# GPIOExpander.net
KiCad netlist of a schematic drawn in Altium Designer
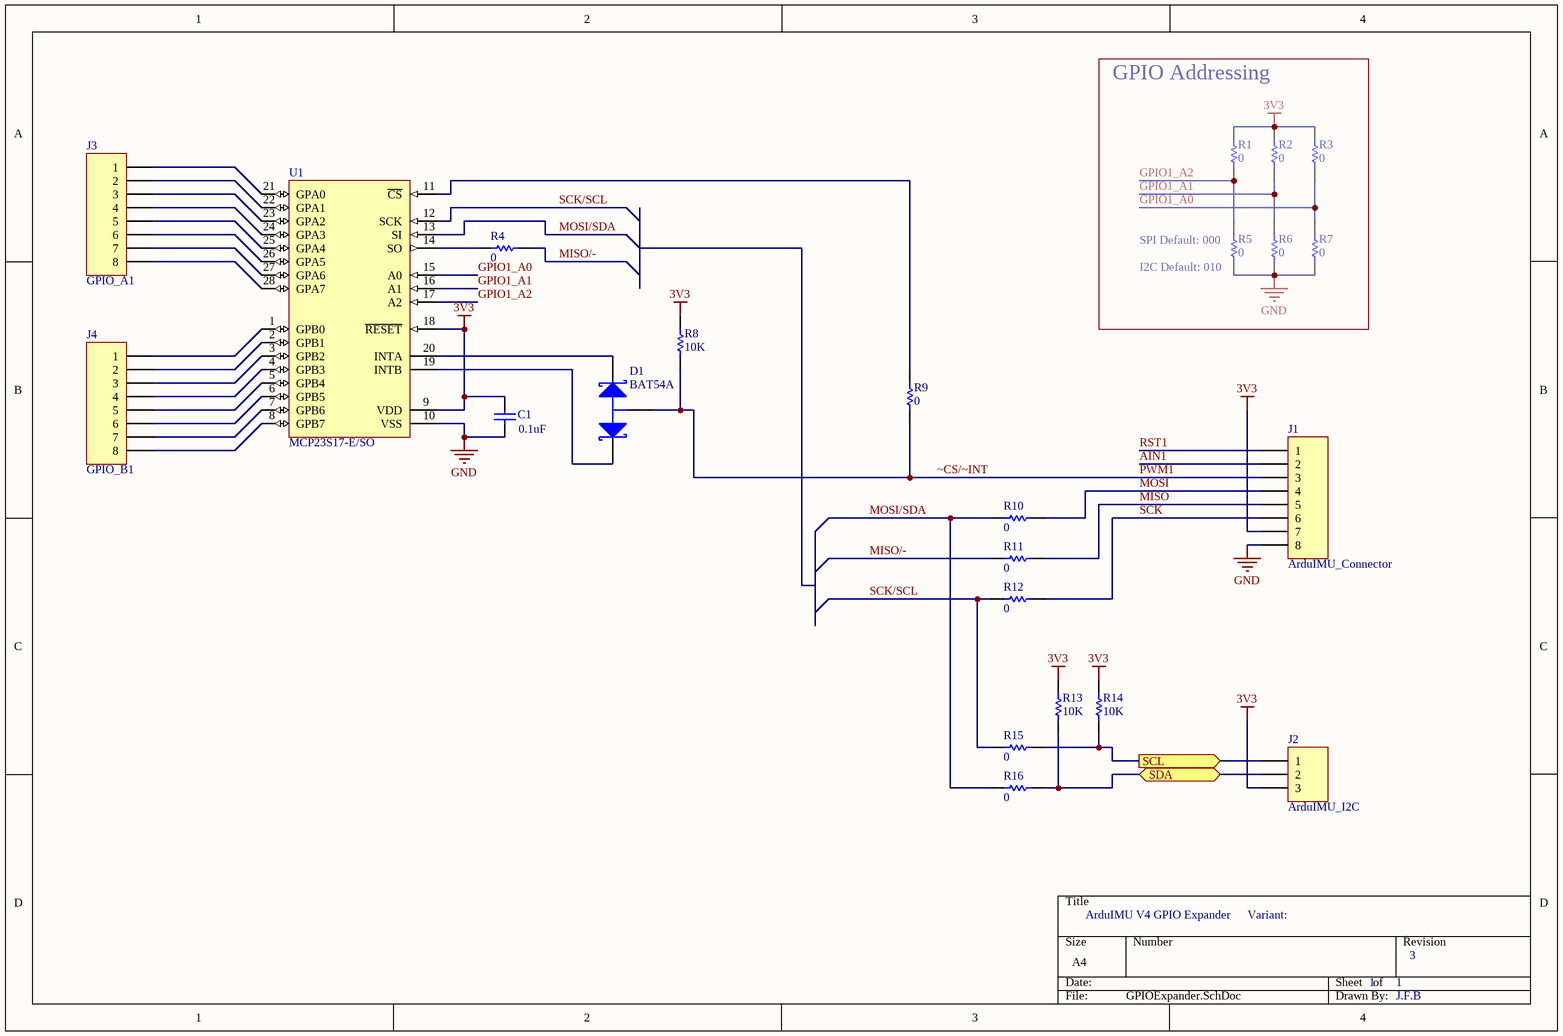
[diagram p0: GPIOExpander.SchDoc]

(export (version "E")
  (design (tool "Eeschema 10.0.6"))
  (components
    (comp (ref "C1")
      (value "0.1uF")
      (footprint "6-0805")
      (description "Capacitor")
      (fields (field (name "Comment") "Cap") (field (name "PUBLISHER") "Altium Limited"))
      (libsource (lib "Miscellaneous Devices") (part "Cap"))
    )
    (comp (ref "D1")
      (value "BAT54A")
      (footprint "SOT23_N")
      (description "Schottky Barrier Double Diode")
      (fields (field (name "PUBLISHER") "Altium Limited"))
      (libsource (lib "Philips Discrete Diode - Schottky") (part "BAT54A"))
    )
    (comp (ref "J1")
      (value "ArduIMU_Connector")
      (footprint "HDR1X8")
      (description "Header, 8-Pin")
      (fields (field (name "PUBLISHER") "Altium Limited"))
      (libsource (lib "Miscellaneous Connectors") (part "Header 8"))
    )
    (comp (ref "J2")
      (value "ArduIMU_I2C")
      (footprint "HDR1X3")
      (description "Header, 3-Pin")
      (fields (field (name "PUBLISHER") "Altium Limited"))
      (libsource (lib "Miscellaneous Connectors") (part "Header 3"))
    )
    (comp (ref "J3")
      (value "GPIO_A1")
      (footprint "HDR1X8")
      (description "Header, 8-Pin")
      (fields (field (name "PUBLISHER") "Altium Limited"))
      (libsource (lib "") (part "Header 8_1"))
    )
    (comp (ref "J4")
      (value "GPIO_B1")
      (footprint "HDR1X8")
      (description "Header, 8-Pin")
      (fields (field (name "PUBLISHER") "Altium Limited"))
      (libsource (lib "") (part "Header 8_1"))
    )
    (comp (ref "R1")
      (value "0")
      (footprint "6-0805")
      (description "Thick Film Chip Resistor, 1 Ohm to 10M Ohm Range, 5% Tolerance, 0805 Size, 0.125 W")
      (fields (field (name "PUBLISHER") "Altium Limited"))
      (libsource (lib "Panasonic Resistor") (part "ERJ6GE"))
    )
    (comp (ref "R2")
      (value "0")
      (footprint "6-0805")
      (description "Thick Film Chip Resistor, 1 Ohm to 10M Ohm Range, 5% Tolerance, 0805 Size, 0.125 W")
      (fields (field (name "PUBLISHER") "Altium Limited"))
      (libsource (lib "Panasonic Resistor") (part "ERJ6GE"))
    )
    (comp (ref "R3")
      (value "0")
      (footprint "6-0805")
      (description "Thick Film Chip Resistor, 1 Ohm to 10M Ohm Range, 5% Tolerance, 0805 Size, 0.125 W")
      (fields (field (name "PUBLISHER") "Altium Limited"))
      (libsource (lib "Panasonic Resistor") (part "ERJ6GE"))
    )
    (comp (ref "R4")
      (value "0")
      (footprint "6-0805")
      (description "Thick Film Chip Resistor, 1 Ohm to 10M Ohm Range, 5% Tolerance, 0805 Size, 0.125 W")
      (fields (field (name "PUBLISHER") "Altium Limited"))
      (libsource (lib "Panasonic Resistor") (part "ERJ6GE"))
    )
    (comp (ref "R5")
      (value "0")
      (footprint "6-0805")
      (description "Thick Film Chip Resistor, 1 Ohm to 10M Ohm Range, 5% Tolerance, 0805 Size, 0.125 W")
      (fields (field (name "PUBLISHER") "Altium Limited"))
      (libsource (lib "Panasonic Resistor") (part "ERJ6GE"))
    )
    (comp (ref "R6")
      (value "0")
      (footprint "6-0805")
      (description "Thick Film Chip Resistor, 1 Ohm to 10M Ohm Range, 5% Tolerance, 0805 Size, 0.125 W")
      (fields (field (name "PUBLISHER") "Altium Limited"))
      (libsource (lib "Panasonic Resistor") (part "ERJ6GE"))
    )
    (comp (ref "R7")
      (value "0")
      (footprint "6-0805")
      (description "Thick Film Chip Resistor, 1 Ohm to 10M Ohm Range, 5% Tolerance, 0805 Size, 0.125 W")
      (fields (field (name "PUBLISHER") "Altium Limited"))
      (libsource (lib "Panasonic Resistor") (part "ERJ6GE"))
    )
    (comp (ref "R8")
      (value "10K")
      (footprint "8-1206")
      (description "Thick Film Chip Resistor, 1 Ohm to 10M Ohm Range, 5% Tolerance, 1206 Size, 0.25 W")
      (fields (field (name "PUBLISHER") "Altium Limited"))
      (libsource (lib "Panasonic Resistor") (part "ERJ8GE"))
    )
    (comp (ref "R9")
      (value "0")
      (footprint "6-0805")
      (description "Thick Film Chip Resistor, 1 Ohm to 10M Ohm Range, 5% Tolerance, 0805 Size, 0.125 W")
      (fields (field (name "PUBLISHER") "Altium Limited"))
      (libsource (lib "Panasonic Resistor") (part "ERJ6GE"))
    )
    (comp (ref "R10")
      (value "0")
      (footprint "6-0805")
      (description "Thick Film Chip Resistor, 1 Ohm to 10M Ohm Range, 5% Tolerance, 0805 Size, 0.125 W")
      (fields (field (name "PUBLISHER") "Altium Limited"))
      (libsource (lib "Panasonic Resistor") (part "ERJ6GE"))
    )
    (comp (ref "R11")
      (value "0")
      (footprint "6-0805")
      (description "Thick Film Chip Resistor, 1 Ohm to 10M Ohm Range, 5% Tolerance, 0805 Size, 0.125 W")
      (fields (field (name "PUBLISHER") "Altium Limited"))
      (libsource (lib "Panasonic Resistor") (part "ERJ6GE"))
    )
    (comp (ref "R12")
      (value "0")
      (footprint "6-0805")
      (description "Thick Film Chip Resistor, 1 Ohm to 10M Ohm Range, 5% Tolerance, 0805 Size, 0.125 W")
      (fields (field (name "PUBLISHER") "Altium Limited"))
      (libsource (lib "Panasonic Resistor") (part "ERJ6GE"))
    )
    (comp (ref "R13")
      (value "10K")
      (footprint "8-1206")
      (description "Thick Film Chip Resistor, 1 Ohm to 10M Ohm Range, 5% Tolerance, 1206 Size, 0.25 W")
      (fields (field (name "PUBLISHER") "Altium Limited"))
      (libsource (lib "Panasonic Resistor") (part "ERJ8GE"))
    )
    (comp (ref "R14")
      (value "10K")
      (footprint "8-1206")
      (description "Thick Film Chip Resistor, 1 Ohm to 10M Ohm Range, 5% Tolerance, 1206 Size, 0.25 W")
      (fields (field (name "PUBLISHER") "Altium Limited"))
      (libsource (lib "Panasonic Resistor") (part "ERJ8GE"))
    )
    (comp (ref "R15")
      (value "0")
      (footprint "6-0805")
      (description "Thick Film Chip Resistor, 1 Ohm to 10M Ohm Range, 5% Tolerance, 0805 Size, 0.125 W")
      (fields (field (name "PUBLISHER") "Altium Limited"))
      (libsource (lib "Panasonic Resistor") (part "ERJ6GE"))
    )
    (comp (ref "R16")
      (value "0")
      (footprint "6-0805")
      (description "Thick Film Chip Resistor, 1 Ohm to 10M Ohm Range, 5% Tolerance, 0805 Size, 0.125 W")
      (fields (field (name "PUBLISHER") "Altium Limited"))
      (libsource (lib "Panasonic Resistor") (part "ERJ6GE"))
    )
    (comp (ref "U1")
      (value "MCP23S17-E/SO")
      (footprint "SOIC-SO28_N")
      (description "16-Bit I/O Expander with Serial Interface, 28-Pin SOIC, Extended Temperature")
      (fields (field (name "PUBLISHER") "Altium Limited"))
      (libsource (lib "Microchip Interface") (part "MCP23S17-E/SO"))
    )
  )
  (nets
    (net (code "1") (name "/AIN1") (class "Default")
      (node (ref "J1") (pin "2") (pinfunction "2_2") (pintype "passive"))
    )
    (net (code "2") (name "/GPIO1_A0") (class "Default")
      (node (ref "R3") (pin "1") (pinfunction "1_1") (pintype "passive"))
      (node (ref "R7") (pin "2") (pinfunction "2_2") (pintype "passive"))
      (node (ref "U1") (pin "15") (pinfunction "A0_15") (pintype "input"))
    )
    (net (code "3") (name "/GPIO1_A1") (class "Default")
      (node (ref "R2") (pin "1") (pinfunction "1_1") (pintype "passive"))
      (node (ref "R6") (pin "2") (pinfunction "2_2") (pintype "passive"))
      (node (ref "U1") (pin "16") (pinfunction "A1_16") (pintype "input"))
    )
    (net (code "4") (name "/GPIO1_A2") (class "Default")
      (node (ref "R1") (pin "1") (pinfunction "1_1") (pintype "passive"))
      (node (ref "R5") (pin "2") (pinfunction "2_2") (pintype "passive"))
      (node (ref "U1") (pin "17") (pinfunction "A2_17") (pintype "input"))
    )
    (net (code "5") (name "/MISO") (class "Default")
      (node (ref "J1") (pin "5") (pinfunction "5_5") (pintype "passive"))
      (node (ref "R11") (pin "2") (pinfunction "2_2") (pintype "passive"))
    )
    (net (code "6") (name "/MISO{slash}-") (class "Default")
      (node (ref "R11") (pin "1") (pinfunction "1_1") (pintype "passive"))
      (node (ref "R4") (pin "2") (pinfunction "2_2") (pintype "passive"))
    )
    (net (code "7") (name "/MOSI") (class "Default")
      (node (ref "J1") (pin "4") (pinfunction "4_4") (pintype "passive"))
      (node (ref "R10") (pin "2") (pinfunction "2_2") (pintype "passive"))
    )
    (net (code "8") (name "/MOSI{slash}SDA") (class "Default")
      (node (ref "R10") (pin "1") (pinfunction "1_1") (pintype "passive"))
      (node (ref "R16") (pin "1") (pinfunction "1_1") (pintype "passive"))
      (node (ref "U1") (pin "13") (pinfunction "SI_13") (pintype "input"))
    )
    (net (code "9") (name "/PWM1") (class "Default")
      (node (ref "D1") (pin "3") (pinfunction "A_3") (pintype "passive"))
      (node (ref "J1") (pin "3") (pinfunction "3_3") (pintype "passive"))
      (node (ref "R8") (pin "2") (pinfunction "2_2") (pintype "passive"))
      (node (ref "R9") (pin "1") (pinfunction "1_1") (pintype "passive"))
    )
    (net (code "10") (name "/RST1") (class "Default")
      (node (ref "J1") (pin "1") (pinfunction "1_1") (pintype "passive"))
    )
    (net (code "11") (name "/SCK") (class "Default")
      (node (ref "J1") (pin "6") (pinfunction "6_6") (pintype "passive"))
      (node (ref "R12") (pin "2") (pinfunction "2_2") (pintype "passive"))
    )
    (net (code "12") (name "/SCK{slash}SCL") (class "Default")
      (node (ref "R12") (pin "1") (pinfunction "1_1") (pintype "passive"))
      (node (ref "R15") (pin "1") (pinfunction "1_1") (pintype "passive"))
      (node (ref "U1") (pin "12") (pinfunction "SCK_12") (pintype "input"))
    )
    (net (code "13") (name "/SCL") (class "Default")
      (node (ref "J2") (pin "1") (pinfunction "1_1") (pintype "passive"))
      (node (ref "R14") (pin "2") (pinfunction "2_2") (pintype "passive"))
      (node (ref "R15") (pin "2") (pinfunction "2_2") (pintype "passive"))
    )
    (net (code "14") (name "/SDA") (class "Default")
      (node (ref "J2") (pin "2") (pinfunction "2_2") (pintype "passive"))
      (node (ref "R13") (pin "2") (pinfunction "2_2") (pintype "passive"))
      (node (ref "R16") (pin "2") (pinfunction "2_2") (pintype "passive"))
    )
    (net (code "15") (name "3V3") (class "Default")
      (node (ref "C1") (pin "2") (pinfunction "2_2") (pintype "passive"))
      (node (ref "J1") (pin "7") (pinfunction "7_7") (pintype "passive"))
      (node (ref "J2") (pin "3") (pinfunction "3_3") (pintype "passive"))
      (node (ref "R1") (pin "2") (pinfunction "2_2") (pintype "passive"))
      (node (ref "R13") (pin "1") (pinfunction "1_1") (pintype "passive"))
      (node (ref "R14") (pin "1") (pinfunction "1_1") (pintype "passive"))
      (node (ref "R2") (pin "2") (pinfunction "2_2") (pintype "passive"))
      (node (ref "R3") (pin "2") (pinfunction "2_2") (pintype "passive"))
      (node (ref "R8") (pin "1") (pinfunction "1_1") (pintype "passive"))
      (node (ref "U1") (pin "18") (pinfunction "~{RESET}_18") (pintype "input"))
      (node (ref "U1") (pin "9") (pinfunction "VDD_9") (pintype "power_in"))
    )
    (net (code "16") (name "GND") (class "Default")
      (node (ref "C1") (pin "1") (pinfunction "1_1") (pintype "passive"))
      (node (ref "J1") (pin "8") (pinfunction "8_8") (pintype "passive"))
      (node (ref "R5") (pin "1") (pinfunction "1_1") (pintype "passive"))
      (node (ref "R6") (pin "1") (pinfunction "1_1") (pintype "passive"))
      (node (ref "R7") (pin "1") (pinfunction "1_1") (pintype "passive"))
      (node (ref "U1") (pin "10") (pinfunction "VSS_10") (pintype "power_in"))
    )
    (net (code "17") (name "Net-(D1-K1)") (class "Default")
      (node (ref "D1") (pin "1") (pinfunction "K1_1") (pintype "passive"))
      (node (ref "U1") (pin "20") (pinfunction "INTA_20") (pintype "open_collector"))
    )
    (net (code "18") (name "Net-(D1-K2)") (class "Default")
      (node (ref "D1") (pin "2") (pinfunction "K2_2") (pintype "passive"))
      (node (ref "U1") (pin "19") (pinfunction "INTB_19") (pintype "open_collector"))
    )
    (net (code "19") (name "Net-(U1-GPA0)") (class "Default")
      (node (ref "J3") (pin "1") (pinfunction "1_1") (pintype "passive"))
      (node (ref "U1") (pin "21") (pinfunction "GPA0_21") (pintype "bidirectional"))
    )
    (net (code "20") (name "Net-(U1-GPA1)") (class "Default")
      (node (ref "J3") (pin "2") (pinfunction "2_2") (pintype "passive"))
      (node (ref "U1") (pin "22") (pinfunction "GPA1_22") (pintype "bidirectional"))
    )
    (net (code "21") (name "Net-(U1-GPA2)") (class "Default")
      (node (ref "J3") (pin "3") (pinfunction "3_3") (pintype "passive"))
      (node (ref "U1") (pin "23") (pinfunction "GPA2_23") (pintype "bidirectional"))
    )
    (net (code "22") (name "Net-(U1-GPA3)") (class "Default")
      (node (ref "J3") (pin "4") (pinfunction "4_4") (pintype "passive"))
      (node (ref "U1") (pin "24") (pinfunction "GPA3_24") (pintype "bidirectional"))
    )
    (net (code "23") (name "Net-(U1-GPA4)") (class "Default")
      (node (ref "J3") (pin "5") (pinfunction "5_5") (pintype "passive"))
      (node (ref "U1") (pin "25") (pinfunction "GPA4_25") (pintype "bidirectional"))
    )
    (net (code "24") (name "Net-(U1-GPA5)") (class "Default")
      (node (ref "J3") (pin "6") (pinfunction "6_6") (pintype "passive"))
      (node (ref "U1") (pin "26") (pinfunction "GPA5_26") (pintype "bidirectional"))
    )
    (net (code "25") (name "Net-(U1-GPA6)") (class "Default")
      (node (ref "J3") (pin "7") (pinfunction "7_7") (pintype "passive"))
      (node (ref "U1") (pin "27") (pinfunction "GPA6_27") (pintype "bidirectional"))
    )
    (net (code "26") (name "Net-(U1-GPA7)") (class "Default")
      (node (ref "J3") (pin "8") (pinfunction "8_8") (pintype "passive"))
      (node (ref "U1") (pin "28") (pinfunction "GPA7_28") (pintype "bidirectional"))
    )
    (net (code "27") (name "Net-(U1-GPB0)") (class "Default")
      (node (ref "J4") (pin "1") (pinfunction "1_1") (pintype "passive"))
      (node (ref "U1") (pin "1") (pinfunction "GPB0_1") (pintype "bidirectional"))
    )
    (net (code "28") (name "Net-(U1-GPB1)") (class "Default")
      (node (ref "J4") (pin "2") (pinfunction "2_2") (pintype "passive"))
      (node (ref "U1") (pin "2") (pinfunction "GPB1_2") (pintype "bidirectional"))
    )
    (net (code "29") (name "Net-(U1-GPB2)") (class "Default")
      (node (ref "J4") (pin "3") (pinfunction "3_3") (pintype "passive"))
      (node (ref "U1") (pin "3") (pinfunction "GPB2_3") (pintype "bidirectional"))
    )
    (net (code "30") (name "Net-(U1-GPB3)") (class "Default")
      (node (ref "J4") (pin "4") (pinfunction "4_4") (pintype "passive"))
      (node (ref "U1") (pin "4") (pinfunction "GPB3_4") (pintype "bidirectional"))
    )
    (net (code "31") (name "Net-(U1-GPB4)") (class "Default")
      (node (ref "J4") (pin "5") (pinfunction "5_5") (pintype "passive"))
      (node (ref "U1") (pin "5") (pinfunction "GPB4_5") (pintype "bidirectional"))
    )
    (net (code "32") (name "Net-(U1-GPB5)") (class "Default")
      (node (ref "J4") (pin "6") (pinfunction "6_6") (pintype "passive"))
      (node (ref "U1") (pin "6") (pinfunction "GPB5_6") (pintype "bidirectional"))
    )
    (net (code "33") (name "Net-(U1-GPB6)") (class "Default")
      (node (ref "J4") (pin "7") (pinfunction "7_7") (pintype "passive"))
      (node (ref "U1") (pin "7") (pinfunction "GPB6_7") (pintype "bidirectional"))
    )
    (net (code "34") (name "Net-(U1-GPB7)") (class "Default")
      (node (ref "J4") (pin "8") (pinfunction "8_8") (pintype "passive"))
      (node (ref "U1") (pin "8") (pinfunction "GPB7_8") (pintype "bidirectional"))
    )
    (net (code "35") (name "Net-(U1-SO)") (class "Default")
      (node (ref "R4") (pin "1") (pinfunction "1_1") (pintype "passive"))
      (node (ref "U1") (pin "14") (pinfunction "SO_14") (pintype "output"))
    )
    (net (code "36") (name "Net-(U1-~{CS})") (class "Default")
      (node (ref "R9") (pin "2") (pinfunction "2_2") (pintype "passive"))
      (node (ref "U1") (pin "11") (pinfunction "~{CS}_11") (pintype "input"))
    )
  )
)
